# PCB_3_0.net
KiCad netlist of a schematic drawn in EAGLE
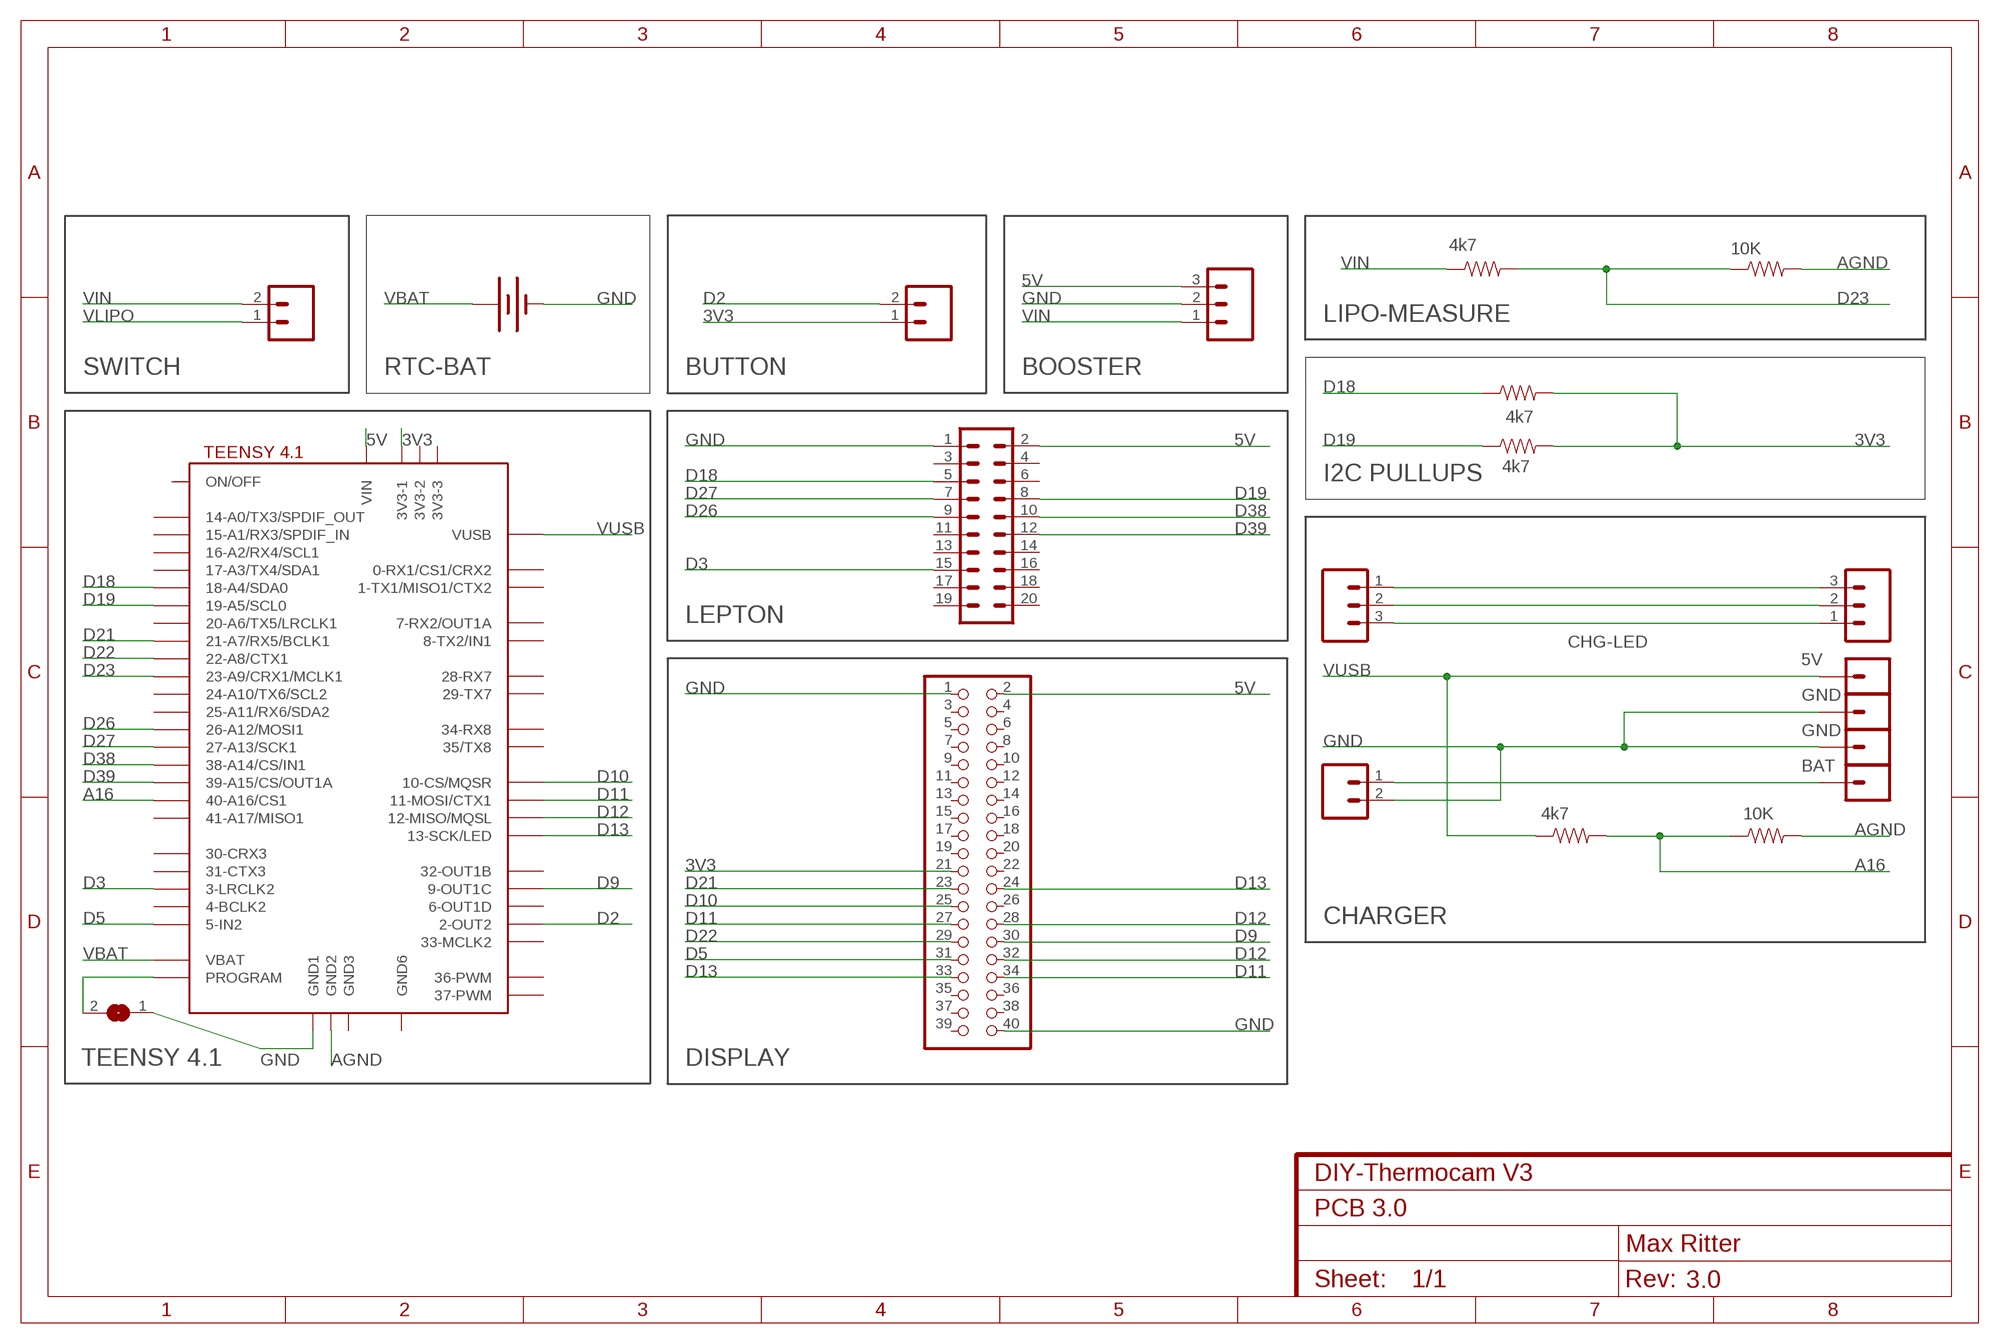
[diagram p0: schematic, sheet 1]

(export (version "E")
  (design (tool "Eeschema 10.0.6"))
  (components
    (comp (ref "BAT")
      (value "BATTERY12PTH")
      (footprint "eagle-import:BATTCON_12MM_PTH")
      (libsource (lib "eagle-import") (part "BATTERY12PTH"))
    )
    (comp (ref "BOOSTER")
      (value "M03PTH")
      (footprint "eagle-import:1X03")
      (libsource (lib "eagle-import") (part "M03PTH"))
    )
    (comp (ref "BUTTON")
      (value "M02PTH")
      (footprint "eagle-import:1X02")
      (libsource (lib "eagle-import") (part "M02PTH"))
    )
    (comp (ref "BUTTON1")
      (value "M02PTH")
      (footprint "eagle-import:1X02")
      (libsource (lib "eagle-import") (part "M02PTH"))
    )
    (comp (ref "CHG-LED")
      (value "M03PTH")
      (footprint "eagle-import:1X03")
      (libsource (lib "eagle-import") (part "M03PTH"))
    )
    (comp (ref "J2")
      (value "CONN_10X2NOSILK")
      (footprint "eagle-import:2X10_NOSILK")
      (libsource (lib "eagle-import") (part "CONN_10X2NOSILK"))
    )
    (comp (ref "JP1")
      (value "M01PTH")
      (footprint "eagle-import:1X01")
      (libsource (lib "eagle-import") (part "M01PTH"))
    )
    (comp (ref "JP2")
      (value "M01PTH")
      (footprint "eagle-import:1X01")
      (libsource (lib "eagle-import") (part "M01PTH"))
    )
    (comp (ref "JP3")
      (value "M01PTH")
      (footprint "eagle-import:1X01")
      (libsource (lib "eagle-import") (part "M01PTH"))
    )
    (comp (ref "JP4")
      (value "M01PTH")
      (footprint "eagle-import:1X01")
      (libsource (lib "eagle-import") (part "M01PTH"))
    )
    (comp (ref "LASER1")
      (value "M03PTH")
      (footprint "eagle-import:1X03")
      (libsource (lib "eagle-import") (part "M03PTH"))
    )
    (comp (ref "LCD-HEADER")
      (value "PINHD-2X20")
      (footprint "eagle-import:2X20")
      (libsource (lib "eagle-import") (part "PINHD-2X20"))
    )
    (comp (ref "PROGRAM")
      (value "SJ")
      (footprint "eagle-import:SJ")
      (libsource (lib "eagle-import") (part "SJ"))
    )
    (comp (ref "R1")
      (value "4k7")
      (footprint "eagle-import:AXIAL-0.4")
      (libsource (lib "eagle-import") (part "RESISTORPTH-1/4W"))
    )
    (comp (ref "R2")
      (value "10K")
      (footprint "eagle-import:AXIAL-0.4")
      (libsource (lib "eagle-import") (part "RESISTORPTH-1/4W"))
    )
    (comp (ref "R3")
      (value "4k7")
      (footprint "eagle-import:AXIAL-0.4")
      (libsource (lib "eagle-import") (part "RESISTORPTH-1/4W"))
    )
    (comp (ref "R4")
      (value "4k7")
      (footprint "eagle-import:AXIAL-0.4")
      (libsource (lib "eagle-import") (part "RESISTORPTH-1/4W"))
    )
    (comp (ref "R5")
      (value "10K")
      (footprint "eagle-import:AXIAL-0.4")
      (libsource (lib "eagle-import") (part "RESISTORPTH-1/4W"))
    )
    (comp (ref "R6")
      (value "4k7")
      (footprint "eagle-import:AXIAL-0.4")
      (libsource (lib "eagle-import") (part "RESISTORPTH-1/4W"))
    )
    (comp (ref "SWITCH")
      (value "M02PTH")
      (footprint "eagle-import:1X02")
      (libsource (lib "eagle-import") (part "M02PTH"))
    )
    (comp (ref "U$2")
      (value "TEENSY41-E")
      (footprint "eagle-import:TENNSY41-E")
      (libsource (lib "eagle-import") (part "TEENSY41-E"))
    )
  )
  (nets
    (net (code "1") (name "/3V3") (class "Default")
      (node (ref "BUTTON") (pin "1") (pinfunction "1_1") (pintype "passive"))
      (node (ref "LCD-HEADER") (pin "21") (pinfunction "21_21") (pintype "passive"))
      (node (ref "R4") (pin "P$2") (pinfunction "2_P$2") (pintype "passive"))
      (node (ref "R6") (pin "P$2") (pinfunction "2_P$2") (pintype "passive"))
      (node (ref "U$2") (pin "3V3-1") (pinfunction "3V3-1_3V3-1") (pintype "bidirectional"))
    )
    (net (code "2") (name "/5V") (class "Default")
      (node (ref "BOOSTER") (pin "3") (pinfunction "3_3") (pintype "passive"))
      (node (ref "J2") (pin "2") (pinfunction "2_2") (pintype "passive"))
      (node (ref "LCD-HEADER") (pin "2") (pinfunction "2_2") (pintype "passive"))
      (node (ref "U$2") (pin "VIN") (pinfunction "VIN_VIN") (pintype "bidirectional"))
    )
    (net (code "3") (name "/A16") (class "Default")
      (node (ref "R3") (pin "P$2") (pinfunction "2_P$2") (pintype "passive"))
      (node (ref "R5") (pin "P$1") (pinfunction "1_P$1") (pintype "passive"))
      (node (ref "U$2") (pin "40-A16/CS1") (pinfunction "40-A16/CS1_40-A16/CS1") (pintype "bidirectional"))
    )
    (net (code "4") (name "/AGND") (class "Default")
      (node (ref "R2") (pin "P$2") (pinfunction "2_P$2") (pintype "passive"))
      (node (ref "R5") (pin "P$2") (pinfunction "2_P$2") (pintype "passive"))
      (node (ref "U$2") (pin "GND2") (pinfunction "GND2_GND2") (pintype "bidirectional"))
    )
    (net (code "5") (name "/D2") (class "Default")
      (node (ref "BUTTON") (pin "2") (pinfunction "2_2") (pintype "passive"))
      (node (ref "U$2") (pin "2-OUT2") (pinfunction "2-OUT2_2-OUT2") (pintype "bidirectional"))
    )
    (net (code "6") (name "/D3") (class "Default")
      (node (ref "J2") (pin "15") (pinfunction "15_15") (pintype "passive"))
      (node (ref "U$2") (pin "3-LRCLK2") (pinfunction "3-LRCLK2_3-LRCLK2") (pintype "bidirectional"))
    )
    (net (code "7") (name "/D5") (class "Default")
      (node (ref "LCD-HEADER") (pin "31") (pinfunction "31_31") (pintype "passive"))
      (node (ref "U$2") (pin "5-IN2") (pinfunction "5-IN2_5-IN2") (pintype "bidirectional"))
    )
    (net (code "8") (name "/D9") (class "Default")
      (node (ref "LCD-HEADER") (pin "30") (pinfunction "30_30") (pintype "passive"))
      (node (ref "U$2") (pin "9-OUT1C") (pinfunction "9-OUT1C_9-OUT1C") (pintype "bidirectional"))
    )
    (net (code "9") (name "/D10") (class "Default")
      (node (ref "LCD-HEADER") (pin "25") (pinfunction "25_25") (pintype "passive"))
      (node (ref "U$2") (pin "10-CS\\MQSR") (pinfunction "10-CS/MQSR_10-CS\\MQSR") (pintype "bidirectional"))
    )
    (net (code "10") (name "/D11") (class "Default")
      (node (ref "LCD-HEADER") (pin "27") (pinfunction "27_27") (pintype "passive"))
      (node (ref "LCD-HEADER") (pin "34") (pinfunction "34_34") (pintype "passive"))
      (node (ref "U$2") (pin "11-MOSI/CTX1") (pinfunction "11-MOSI/CTX1_11-MOSI/CTX1") (pintype "bidirectional"))
    )
    (net (code "11") (name "/D12") (class "Default")
      (node (ref "LCD-HEADER") (pin "28") (pinfunction "28_28") (pintype "passive"))
      (node (ref "LCD-HEADER") (pin "32") (pinfunction "32_32") (pintype "passive"))
      (node (ref "U$2") (pin "12-MISO/MQSL") (pinfunction "12-MISO/MQSL_12-MISO/MQSL") (pintype "bidirectional"))
    )
    (net (code "12") (name "/D13") (class "Default")
      (node (ref "LCD-HEADER") (pin "24") (pinfunction "24_24") (pintype "passive"))
      (node (ref "LCD-HEADER") (pin "33") (pinfunction "33_33") (pintype "passive"))
      (node (ref "U$2") (pin "13-SCK/LED") (pinfunction "13-SCK/LED_13-SCK/LED") (pintype "bidirectional"))
    )
    (net (code "13") (name "/D18") (class "Default")
      (node (ref "J2") (pin "5") (pinfunction "5_5") (pintype "passive"))
      (node (ref "R4") (pin "P$1") (pinfunction "1_P$1") (pintype "passive"))
      (node (ref "U$2") (pin "18-A4/SDA0") (pinfunction "18-A4/SDA0_18-A4/SDA0") (pintype "bidirectional"))
    )
    (net (code "14") (name "/D19") (class "Default")
      (node (ref "J2") (pin "8") (pinfunction "8_8") (pintype "passive"))
      (node (ref "R6") (pin "P$1") (pinfunction "1_P$1") (pintype "passive"))
      (node (ref "U$2") (pin "19-A5/SCL0") (pinfunction "19-A5/SCL0_19-A5/SCL0") (pintype "bidirectional"))
    )
    (net (code "15") (name "/D21") (class "Default")
      (node (ref "LCD-HEADER") (pin "23") (pinfunction "23_23") (pintype "passive"))
      (node (ref "U$2") (pin "21-A7/RX5/BCLK1") (pinfunction "21-A7/RX5/BCLK1_21-A7/RX5/BCLK1") (pintype "bidirectional"))
    )
    (net (code "16") (name "/D22") (class "Default")
      (node (ref "LCD-HEADER") (pin "29") (pinfunction "29_29") (pintype "passive"))
      (node (ref "U$2") (pin "22-A8/CTX1") (pinfunction "22-A8/CTX1_22-A8/CTX1") (pintype "bidirectional"))
    )
    (net (code "17") (name "/D23") (class "Default")
      (node (ref "R1") (pin "P$2") (pinfunction "2_P$2") (pintype "passive"))
      (node (ref "R2") (pin "P$1") (pinfunction "1_P$1") (pintype "passive"))
      (node (ref "U$2") (pin "23-A9/CRX1/MCLK1") (pinfunction "23-A9/CRX1/MCLK1_23-A9/CRX1/MCLK1") (pintype "bidirectional"))
    )
    (net (code "18") (name "/D26") (class "Default")
      (node (ref "J2") (pin "9") (pinfunction "9_9") (pintype "passive"))
      (node (ref "U$2") (pin "26-A12/MOSI1") (pinfunction "26-A12/MOSI1_26-A12/MOSI1") (pintype "bidirectional"))
    )
    (net (code "19") (name "/D27") (class "Default")
      (node (ref "J2") (pin "7") (pinfunction "7_7") (pintype "passive"))
      (node (ref "U$2") (pin "27-A13/SCK1") (pinfunction "27-A13/SCK1_27-A13/SCK1") (pintype "bidirectional"))
    )
    (net (code "20") (name "/D38") (class "Default")
      (node (ref "J2") (pin "10") (pinfunction "10_10") (pintype "passive"))
      (node (ref "U$2") (pin "38-A14/CS/IN1") (pinfunction "38-A14/CS/IN1_38-A14/CS/IN1") (pintype "bidirectional"))
    )
    (net (code "21") (name "/D39") (class "Default")
      (node (ref "J2") (pin "12") (pinfunction "12_12") (pintype "passive"))
      (node (ref "U$2") (pin "39-A15/CS/OUT1A") (pinfunction "39-A15/CS/OUT1A_39-A15/CS/OUT1A") (pintype "bidirectional"))
    )
    (net (code "22") (name "/GND") (class "Default")
      (node (ref "BAT") (pin "GND") (pinfunction "-_GND") (pintype "power_in"))
      (node (ref "BOOSTER") (pin "2") (pinfunction "2_2") (pintype "passive"))
      (node (ref "BUTTON1") (pin "2") (pinfunction "2_2") (pintype "passive"))
      (node (ref "J2") (pin "1") (pinfunction "1_1") (pintype "passive"))
      (node (ref "JP1") (pin "1") (pinfunction "1_1") (pintype "passive"))
      (node (ref "JP2") (pin "1") (pinfunction "1_1") (pintype "passive"))
      (node (ref "LCD-HEADER") (pin "1") (pinfunction "1_1") (pintype "passive"))
      (node (ref "LCD-HEADER") (pin "40") (pinfunction "40_40") (pintype "passive"))
      (node (ref "PROGRAM") (pin "1") (pinfunction "1_1") (pintype "passive"))
      (node (ref "U$2") (pin "GND1") (pinfunction "GND1_GND1") (pintype "bidirectional"))
    )
    (net (code "23") (name "/VBAT") (class "Default")
      (node (ref "BAT") (pin "VCC@1") (pinfunction "+_VCC@1") (pintype "power_in"))
      (node (ref "U$2") (pin "VBAT") (pinfunction "VBAT_VBAT") (pintype "bidirectional"))
    )
    (net (code "24") (name "/VIN") (class "Default")
      (node (ref "BOOSTER") (pin "1") (pinfunction "1_1") (pintype "passive"))
      (node (ref "R1") (pin "P$1") (pinfunction "1_P$1") (pintype "passive"))
      (node (ref "SWITCH") (pin "2") (pinfunction "2_2") (pintype "passive"))
    )
    (net (code "25") (name "/VLIPO") (class "Default")
      (node (ref "BUTTON1") (pin "1") (pinfunction "1_1") (pintype "passive"))
      (node (ref "JP3") (pin "1") (pinfunction "1_1") (pintype "passive"))
      (node (ref "SWITCH") (pin "1") (pinfunction "1_1") (pintype "passive"))
    )
    (net (code "26") (name "/VUSB") (class "Default")
      (node (ref "JP4") (pin "1") (pinfunction "1_1") (pintype "passive"))
      (node (ref "R3") (pin "P$1") (pinfunction "1_P$1") (pintype "passive"))
      (node (ref "U$2") (pin "VUSB") (pinfunction "VUSB_VUSB") (pintype "bidirectional"))
    )
    (net (code "27") (name "Net-(CHG-LED-Pad1)") (class "Default")
      (node (ref "CHG-LED") (pin "1") (pinfunction "1_1") (pintype "passive"))
      (node (ref "LASER1") (pin "3") (pinfunction "3_3") (pintype "passive"))
    )
    (net (code "28") (name "Net-(CHG-LED-Pad2)") (class "Default")
      (node (ref "CHG-LED") (pin "2") (pinfunction "2_2") (pintype "passive"))
      (node (ref "LASER1") (pin "2") (pinfunction "2_2") (pintype "passive"))
    )
    (net (code "29") (name "Net-(CHG-LED-Pad3)") (class "Default")
      (node (ref "CHG-LED") (pin "3") (pinfunction "3_3") (pintype "passive"))
      (node (ref "LASER1") (pin "1") (pinfunction "1_1") (pintype "passive"))
    )
    (net (code "30") (name "Net-(PROGRAM-Pad2)") (class "Default")
      (node (ref "PROGRAM") (pin "2") (pinfunction "2_2") (pintype "passive"))
      (node (ref "U$2") (pin "PROGRAM") (pinfunction "PROGRAM_PROGRAM") (pintype "bidirectional"))
    )
    (net (code "31") (name "unconnected-(J2-Pad3)") (class "Default")
      (node (ref "J2") (pin "3") (pinfunction "3_3") (pintype "passive"))
    )
    (net (code "32") (name "unconnected-(J2-Pad4)") (class "Default")
      (node (ref "J2") (pin "4") (pinfunction "4_4") (pintype "passive"))
    )
    (net (code "33") (name "unconnected-(J2-Pad6)") (class "Default")
      (node (ref "J2") (pin "6") (pinfunction "6_6") (pintype "passive"))
    )
    (net (code "34") (name "unconnected-(J2-Pad11)") (class "Default")
      (node (ref "J2") (pin "11") (pinfunction "11_11") (pintype "passive"))
    )
    (net (code "35") (name "unconnected-(J2-Pad13)") (class "Default")
      (node (ref "J2") (pin "13") (pinfunction "13_13") (pintype "passive"))
    )
    (net (code "36") (name "unconnected-(J2-Pad14)") (class "Default")
      (node (ref "J2") (pin "14") (pinfunction "14_14") (pintype "passive"))
    )
    (net (code "37") (name "unconnected-(J2-Pad16)") (class "Default")
      (node (ref "J2") (pin "16") (pinfunction "16_16") (pintype "passive"))
    )
    (net (code "38") (name "unconnected-(J2-Pad17)") (class "Default")
      (node (ref "J2") (pin "17") (pinfunction "17_17") (pintype "passive"))
    )
    (net (code "39") (name "unconnected-(J2-Pad18)") (class "Default")
      (node (ref "J2") (pin "18") (pinfunction "18_18") (pintype "passive"))
    )
    (net (code "40") (name "unconnected-(J2-Pad19)") (class "Default")
      (node (ref "J2") (pin "19") (pinfunction "19_19") (pintype "passive"))
    )
    (net (code "41") (name "unconnected-(J2-Pad20)") (class "Default")
      (node (ref "J2") (pin "20") (pinfunction "20_20") (pintype "passive"))
    )
    (net (code "42") (name "unconnected-(LCD-HEADER-Pad3)") (class "Default")
      (node (ref "LCD-HEADER") (pin "3") (pinfunction "3_3") (pintype "passive"))
    )
    (net (code "43") (name "unconnected-(LCD-HEADER-Pad4)") (class "Default")
      (node (ref "LCD-HEADER") (pin "4") (pinfunction "4_4") (pintype "passive"))
    )
    (net (code "44") (name "unconnected-(LCD-HEADER-Pad5)") (class "Default")
      (node (ref "LCD-HEADER") (pin "5") (pinfunction "5_5") (pintype "passive"))
    )
    (net (code "45") (name "unconnected-(LCD-HEADER-Pad6)") (class "Default")
      (node (ref "LCD-HEADER") (pin "6") (pinfunction "6_6") (pintype "passive"))
    )
    (net (code "46") (name "unconnected-(LCD-HEADER-Pad7)") (class "Default")
      (node (ref "LCD-HEADER") (pin "7") (pinfunction "7_7") (pintype "passive"))
    )
    (net (code "47") (name "unconnected-(LCD-HEADER-Pad8)") (class "Default")
      (node (ref "LCD-HEADER") (pin "8") (pinfunction "8_8") (pintype "passive"))
    )
    (net (code "48") (name "unconnected-(LCD-HEADER-Pad9)") (class "Default")
      (node (ref "LCD-HEADER") (pin "9") (pinfunction "9_9") (pintype "passive"))
    )
    (net (code "49") (name "unconnected-(LCD-HEADER-Pad10)") (class "Default")
      (node (ref "LCD-HEADER") (pin "10") (pinfunction "10_10") (pintype "passive"))
    )
    (net (code "50") (name "unconnected-(LCD-HEADER-Pad11)") (class "Default")
      (node (ref "LCD-HEADER") (pin "11") (pinfunction "11_11") (pintype "passive"))
    )
    (net (code "51") (name "unconnected-(LCD-HEADER-Pad12)") (class "Default")
      (node (ref "LCD-HEADER") (pin "12") (pinfunction "12_12") (pintype "passive"))
    )
    (net (code "52") (name "unconnected-(LCD-HEADER-Pad13)") (class "Default")
      (node (ref "LCD-HEADER") (pin "13") (pinfunction "13_13") (pintype "passive"))
    )
    (net (code "53") (name "unconnected-(LCD-HEADER-Pad14)") (class "Default")
      (node (ref "LCD-HEADER") (pin "14") (pinfunction "14_14") (pintype "passive"))
    )
    (net (code "54") (name "unconnected-(LCD-HEADER-Pad15)") (class "Default")
      (node (ref "LCD-HEADER") (pin "15") (pinfunction "15_15") (pintype "passive"))
    )
    (net (code "55") (name "unconnected-(LCD-HEADER-Pad16)") (class "Default")
      (node (ref "LCD-HEADER") (pin "16") (pinfunction "16_16") (pintype "passive"))
    )
    (net (code "56") (name "unconnected-(LCD-HEADER-Pad17)") (class "Default")
      (node (ref "LCD-HEADER") (pin "17") (pinfunction "17_17") (pintype "passive"))
    )
    (net (code "57") (name "unconnected-(LCD-HEADER-Pad18)") (class "Default")
      (node (ref "LCD-HEADER") (pin "18") (pinfunction "18_18") (pintype "passive"))
    )
    (net (code "58") (name "unconnected-(LCD-HEADER-Pad19)") (class "Default")
      (node (ref "LCD-HEADER") (pin "19") (pinfunction "19_19") (pintype "passive"))
    )
    (net (code "59") (name "unconnected-(LCD-HEADER-Pad20)") (class "Default")
      (node (ref "LCD-HEADER") (pin "20") (pinfunction "20_20") (pintype "passive"))
    )
    (net (code "60") (name "unconnected-(LCD-HEADER-Pad22)") (class "Default")
      (node (ref "LCD-HEADER") (pin "22") (pinfunction "22_22") (pintype "passive"))
    )
    (net (code "61") (name "unconnected-(LCD-HEADER-Pad26)") (class "Default")
      (node (ref "LCD-HEADER") (pin "26") (pinfunction "26_26") (pintype "passive"))
    )
    (net (code "62") (name "unconnected-(LCD-HEADER-Pad35)") (class "Default")
      (node (ref "LCD-HEADER") (pin "35") (pinfunction "35_35") (pintype "passive"))
    )
    (net (code "63") (name "unconnected-(LCD-HEADER-Pad36)") (class "Default")
      (node (ref "LCD-HEADER") (pin "36") (pinfunction "36_36") (pintype "passive"))
    )
    (net (code "64") (name "unconnected-(LCD-HEADER-Pad37)") (class "Default")
      (node (ref "LCD-HEADER") (pin "37") (pinfunction "37_37") (pintype "passive"))
    )
    (net (code "65") (name "unconnected-(LCD-HEADER-Pad38)") (class "Default")
      (node (ref "LCD-HEADER") (pin "38") (pinfunction "38_38") (pintype "passive"))
    )
    (net (code "66") (name "unconnected-(LCD-HEADER-Pad39)") (class "Default")
      (node (ref "LCD-HEADER") (pin "39") (pinfunction "39_39") (pintype "passive"))
    )
    (net (code "67") (name "unconnected-(U$2-35{slash}TX8-Pad35-TX8)") (class "Default")
      (node (ref "U$2") (pin "35-TX8") (pinfunction "35/TX8_35-TX8") (pintype "bidirectional"))
    )
    (net (code "68") (name "unconnected-(U$2-Pad0-RX1{slash}CS1{slash}CRX2)") (class "Default")
      (node (ref "U$2") (pin "0-RX1/CS1/CRX2") (pinfunction "0-RX1/CS1/CRX2_0-RX1/CS1/CRX2") (pintype "bidirectional"))
    )
    (net (code "69") (name "unconnected-(U$2-Pad1-TX1{slash}MISO1{slash}CTX2)") (class "Default")
      (node (ref "U$2") (pin "1-TX1/MISO1/CTX2") (pinfunction "1-TX1/MISO1/CTX2_1-TX1/MISO1/CTX2") (pintype "bidirectional"))
    )
    (net (code "70") (name "unconnected-(U$2-Pad3V3-2)") (class "Default")
      (node (ref "U$2") (pin "3V3-2") (pinfunction "3V3-2_3V3-2") (pintype "bidirectional"))
    )
    (net (code "71") (name "unconnected-(U$2-Pad3V3-3)") (class "Default")
      (node (ref "U$2") (pin "3V3-3") (pinfunction "3V3-3_3V3-3") (pintype "bidirectional"))
    )
    (net (code "72") (name "unconnected-(U$2-Pad4-BCLK2)") (class "Default")
      (node (ref "U$2") (pin "4-BCLK2") (pinfunction "4-BCLK2_4-BCLK2") (pintype "bidirectional"))
    )
    (net (code "73") (name "unconnected-(U$2-Pad6-OUT1D)") (class "Default")
      (node (ref "U$2") (pin "6-OUT1D") (pinfunction "6-OUT1D_6-OUT1D") (pintype "bidirectional"))
    )
    (net (code "74") (name "unconnected-(U$2-Pad7-RX2{slash}OUT1A)") (class "Default")
      (node (ref "U$2") (pin "7-RX2/OUT1A") (pinfunction "7-RX2/OUT1A_7-RX2/OUT1A") (pintype "bidirectional"))
    )
    (net (code "75") (name "unconnected-(U$2-Pad8-TX2{slash}IN1)") (class "Default")
      (node (ref "U$2") (pin "8-TX2/IN1") (pinfunction "8-TX2/IN1_8-TX2/IN1") (pintype "bidirectional"))
    )
    (net (code "76") (name "unconnected-(U$2-Pad14-A0{slash}TX3{slash}SPDIF_OUT)") (class "Default")
      (node (ref "U$2") (pin "14-A0/TX3/SPDIF_OUT") (pinfunction "14-A0/TX3/SPDIF_OUT_14-A0/TX3/SPDIF_OUT") (pintype "bidirectional"))
    )
    (net (code "77") (name "unconnected-(U$2-Pad15-A1{slash}RX3{slash}SPDIF_IN)") (class "Default")
      (node (ref "U$2") (pin "15-A1/RX3/SPDIF_IN") (pinfunction "15-A1/RX3/SPDIF_IN_15-A1/RX3/SPDIF_IN") (pintype "bidirectional"))
    )
    (net (code "78") (name "unconnected-(U$2-Pad16-A2{slash}RX4{slash}SCL1)") (class "Default")
      (node (ref "U$2") (pin "16-A2/RX4/SCL1") (pinfunction "16-A2/RX4/SCL1_16-A2/RX4/SCL1") (pintype "bidirectional"))
    )
    (net (code "79") (name "unconnected-(U$2-Pad17-A3{slash}TX4{slash}SDA1)") (class "Default")
      (node (ref "U$2") (pin "17-A3/TX4/SDA1") (pinfunction "17-A3/TX4/SDA1_17-A3/TX4/SDA1") (pintype "bidirectional"))
    )
    (net (code "80") (name "unconnected-(U$2-Pad20-A6{slash}TX5{slash}LRCLK1)") (class "Default")
      (node (ref "U$2") (pin "20-A6/TX5/LRCLK1") (pinfunction "20-A6/TX5/LRCLK1_20-A6/TX5/LRCLK1") (pintype "bidirectional"))
    )
    (net (code "81") (name "unconnected-(U$2-Pad24-A10{slash}TX6{slash}SCL2)") (class "Default")
      (node (ref "U$2") (pin "24-A10/TX6/SCL2") (pinfunction "24-A10/TX6/SCL2_24-A10/TX6/SCL2") (pintype "bidirectional"))
    )
    (net (code "82") (name "unconnected-(U$2-Pad25-A11{slash}RX6{slash}SDA2)") (class "Default")
      (node (ref "U$2") (pin "25-A11/RX6/SDA2") (pinfunction "25-A11/RX6/SDA2_25-A11/RX6/SDA2") (pintype "bidirectional"))
    )
    (net (code "83") (name "unconnected-(U$2-Pad28-RX7)") (class "Default")
      (node (ref "U$2") (pin "28-RX7") (pinfunction "28-RX7_28-RX7") (pintype "bidirectional"))
    )
    (net (code "84") (name "unconnected-(U$2-Pad29-TX7)") (class "Default")
      (node (ref "U$2") (pin "29-TX7") (pinfunction "29-TX7_29-TX7") (pintype "bidirectional"))
    )
    (net (code "85") (name "unconnected-(U$2-Pad30-CRX3)") (class "Default")
      (node (ref "U$2") (pin "30-CRX3") (pinfunction "30-CRX3_30-CRX3") (pintype "bidirectional"))
    )
    (net (code "86") (name "unconnected-(U$2-Pad31-CTX3)") (class "Default")
      (node (ref "U$2") (pin "31-CTX3") (pinfunction "31-CTX3_31-CTX3") (pintype "bidirectional"))
    )
    (net (code "87") (name "unconnected-(U$2-Pad32-OUT1B)") (class "Default")
      (node (ref "U$2") (pin "32-OUT1B") (pinfunction "32-OUT1B_32-OUT1B") (pintype "bidirectional"))
    )
    (net (code "88") (name "unconnected-(U$2-Pad33-MCLK2)") (class "Default")
      (node (ref "U$2") (pin "33-MCLK2") (pinfunction "33-MCLK2_33-MCLK2") (pintype "bidirectional"))
    )
    (net (code "89") (name "unconnected-(U$2-Pad34-RX8)") (class "Default")
      (node (ref "U$2") (pin "34-RX8") (pinfunction "34-RX8_34-RX8") (pintype "bidirectional"))
    )
    (net (code "90") (name "unconnected-(U$2-Pad36-PWM)") (class "Default")
      (node (ref "U$2") (pin "36-PWM") (pinfunction "36-PWM_36-PWM") (pintype "bidirectional"))
    )
    (net (code "91") (name "unconnected-(U$2-Pad37-PWM)") (class "Default")
      (node (ref "U$2") (pin "37-PWM") (pinfunction "37-PWM_37-PWM") (pintype "bidirectional"))
    )
    (net (code "92") (name "unconnected-(U$2-Pad41-A17{slash}MISO1)") (class "Default")
      (node (ref "U$2") (pin "41-A17/MISO1") (pinfunction "41-A17/MISO1_41-A17/MISO1") (pintype "bidirectional"))
    )
    (net (code "93") (name "unconnected-(U$2-PadGND3)") (class "Default")
      (node (ref "U$2") (pin "GND3") (pinfunction "GND3_GND3") (pintype "bidirectional"))
    )
    (net (code "94") (name "unconnected-(U$2-PadGND6)") (class "Default")
      (node (ref "U$2") (pin "GND6") (pinfunction "GND6_GND6") (pintype "bidirectional"))
    )
    (net (code "95") (name "unconnected-(U$2-PadON{slash}OFF)") (class "Default")
      (node (ref "U$2") (pin "ON/OFF") (pinfunction "ON/OFF_ON/OFF") (pintype "bidirectional"))
    )
  )
)
